# analog_part.net
KiCad netlist of a schematic drawn in Altium Designer
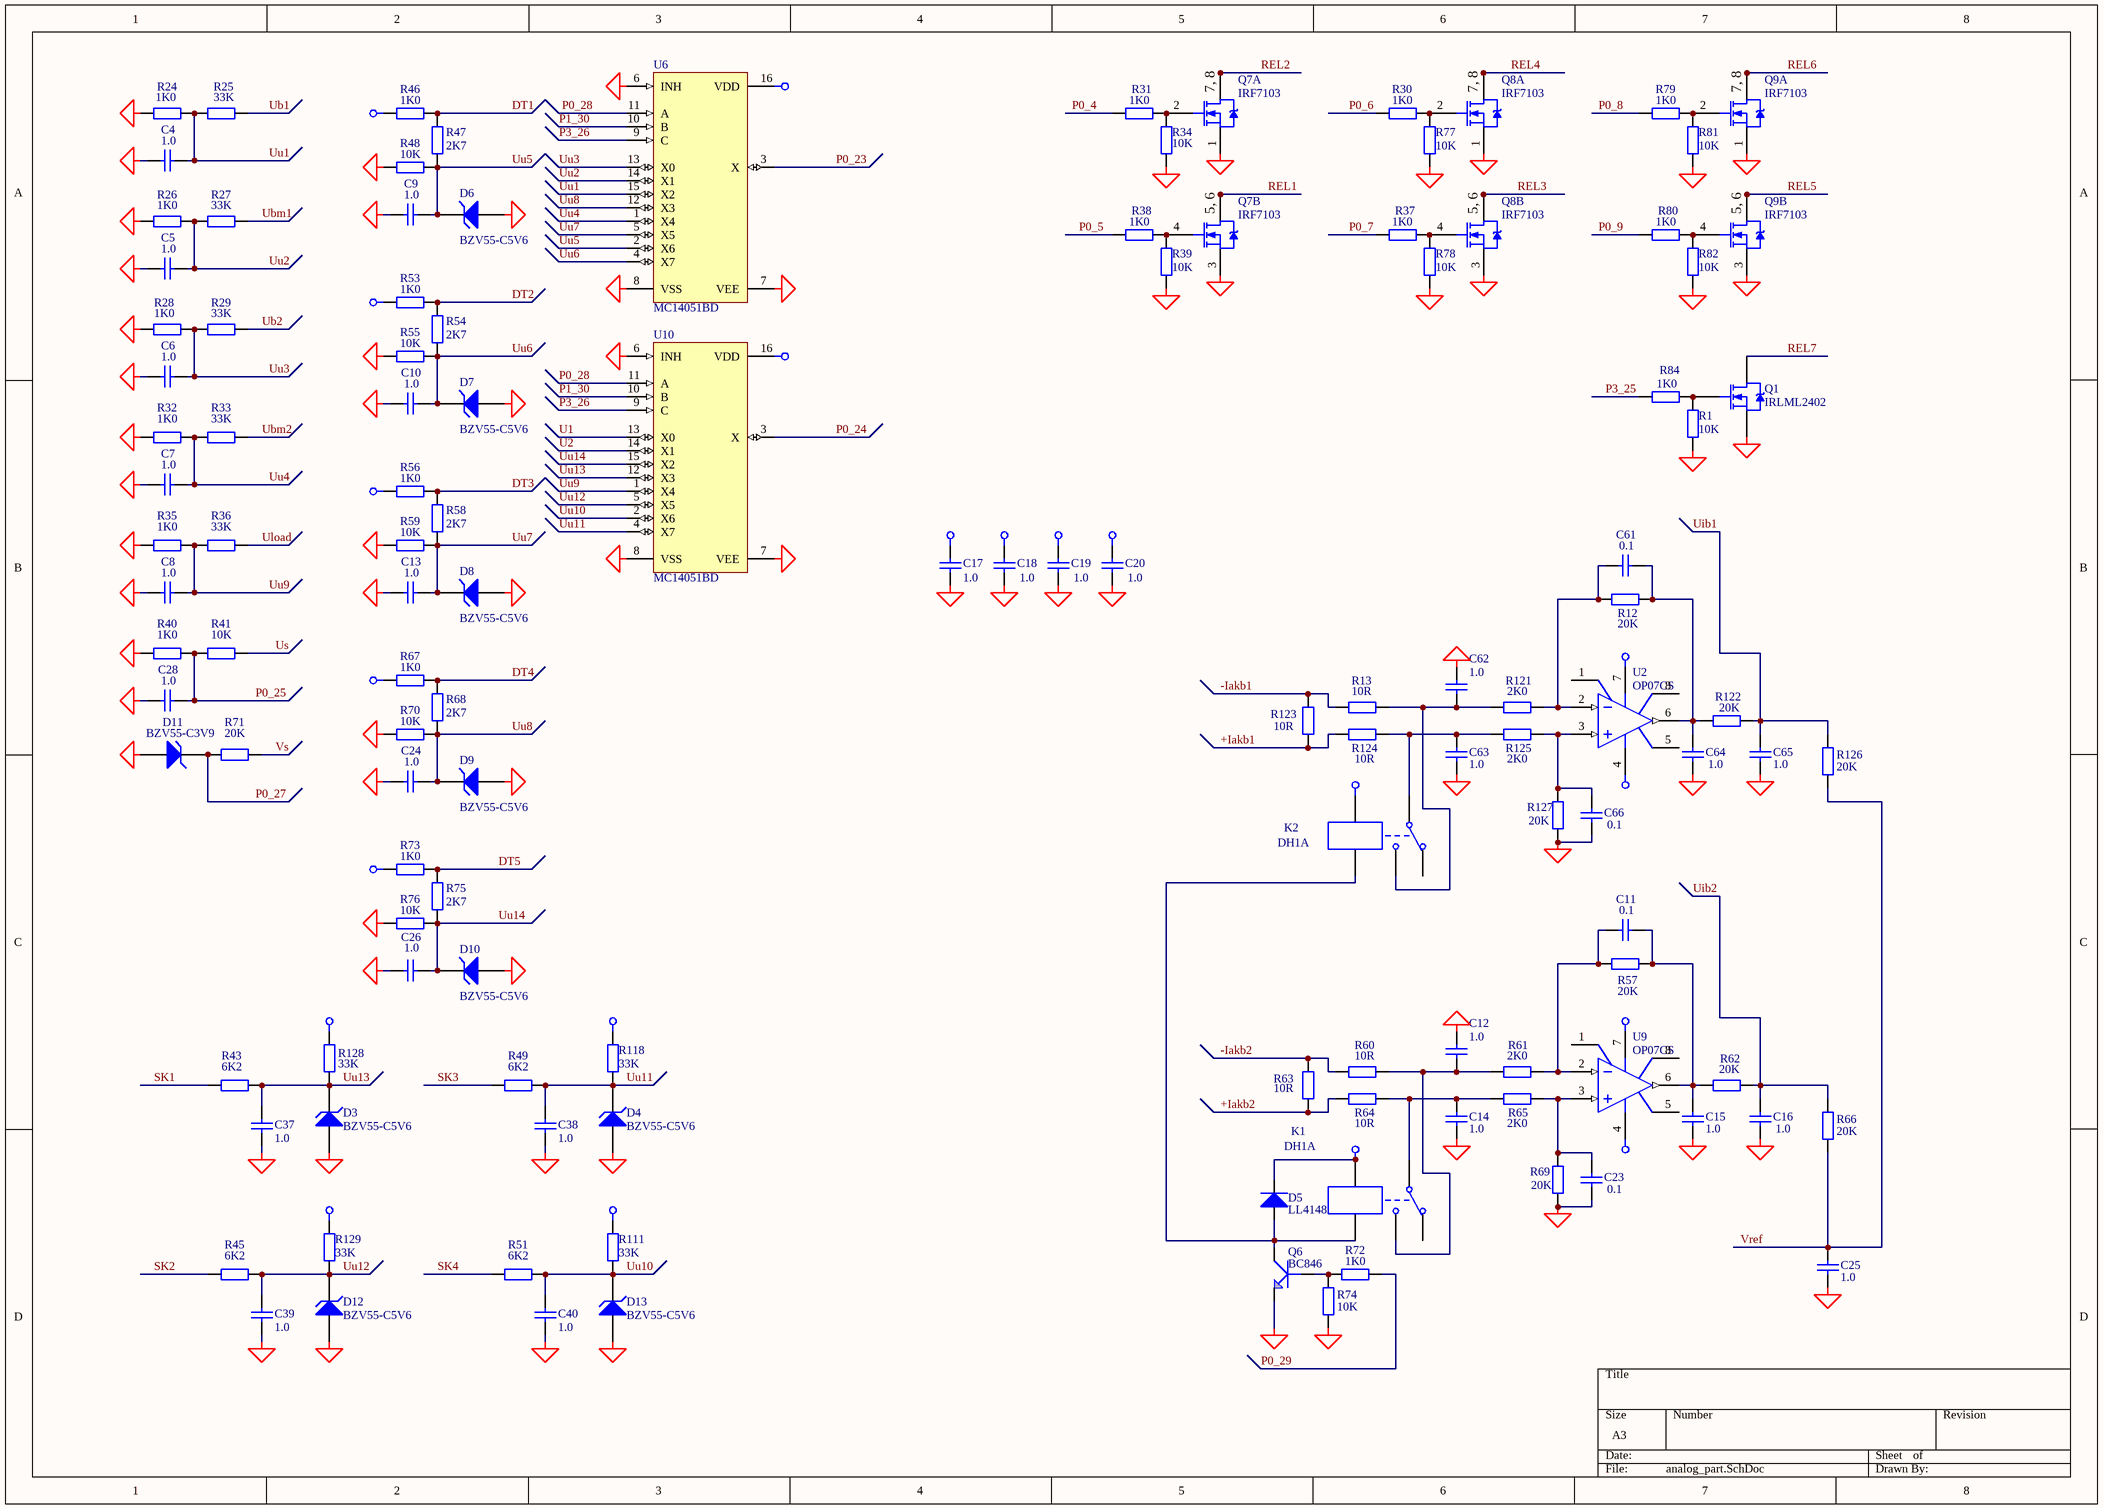
[diagram p0: analog_part.SchDoc]

(export (version "E")
  (design (tool "Eeschema 10.0.6"))
  (components
    (comp (ref "C4")
      (value "1.0")
      (footprint "_1206")
      (description "Capacitor")
      (fields (field (name "MANUFACTURER") "Generic Components"))
      (libsource (lib "Miscellaneous Devices") (part "Cap Semi"))
    )
    (comp (ref "C5")
      (value "1.0")
      (footprint "_1206")
      (description "Capacitor")
      (fields (field (name "MANUFACTURER") "Generic Components"))
      (libsource (lib "Miscellaneous Devices") (part "Cap Semi"))
    )
    (comp (ref "C6")
      (value "1.0")
      (footprint "_1206")
      (description "Capacitor")
      (fields (field (name "MANUFACTURER") "Generic Components"))
      (libsource (lib "Miscellaneous Devices") (part "Cap Semi"))
    )
    (comp (ref "C7")
      (value "1.0")
      (footprint "_1206")
      (description "Capacitor")
      (fields (field (name "MANUFACTURER") "Generic Components"))
      (libsource (lib "Miscellaneous Devices") (part "Cap Semi"))
    )
    (comp (ref "C8")
      (value "1.0")
      (footprint "_1206")
      (description "Capacitor")
      (fields (field (name "MANUFACTURER") "Generic Components"))
      (libsource (lib "Miscellaneous Devices") (part "Cap Semi"))
    )
    (comp (ref "C9")
      (value "1.0")
      (footprint "_1206")
      (description "Capacitor")
      (fields (field (name "MANUFACTURER") "Generic Components"))
      (libsource (lib "Miscellaneous Devices") (part "Cap Semi"))
    )
    (comp (ref "C10")
      (value "1.0")
      (footprint "_1206")
      (description "Capacitor")
      (fields (field (name "MANUFACTURER") "Generic Components"))
      (libsource (lib "Miscellaneous Devices") (part "Cap Semi"))
    )
    (comp (ref "C11")
      (value "0.1")
      (footprint "_1206")
      (description "Capacitor")
      (fields (field (name "MANUFACTURER") "Generic Components"))
      (libsource (lib "Miscellaneous Devices") (part "Cap Semi"))
    )
    (comp (ref "C12")
      (value "1.0")
      (footprint "_1206")
      (description "Capacitor")
      (fields (field (name "MANUFACTURER") "Generic Components"))
      (libsource (lib "Miscellaneous Devices") (part "Cap Semi"))
    )
    (comp (ref "C13")
      (value "1.0")
      (footprint "_1206")
      (description "Capacitor")
      (fields (field (name "MANUFACTURER") "Generic Components"))
      (libsource (lib "Miscellaneous Devices") (part "Cap Semi"))
    )
    (comp (ref "C14")
      (value "1.0")
      (footprint "_1206")
      (description "Capacitor")
      (fields (field (name "MANUFACTURER") "Generic Components"))
      (libsource (lib "Miscellaneous Devices") (part "Cap Semi"))
    )
    (comp (ref "C15")
      (value "1.0")
      (footprint "_1206")
      (description "Capacitor")
      (fields (field (name "MANUFACTURER") "Generic Components"))
      (libsource (lib "Miscellaneous Devices") (part "Cap Semi"))
    )
    (comp (ref "C16")
      (value "1.0")
      (footprint "_1206")
      (description "Capacitor")
      (fields (field (name "MANUFACTURER") "Generic Components"))
      (libsource (lib "Miscellaneous Devices") (part "Cap Semi"))
    )
    (comp (ref "C17")
      (value "1.0")
      (footprint "_1206")
      (description "Capacitor")
      (fields (field (name "MANUFACTURER") "Generic Components"))
      (libsource (lib "Miscellaneous Devices") (part "Cap Semi"))
    )
    (comp (ref "C18")
      (value "1.0")
      (footprint "_1206")
      (description "Capacitor")
      (fields (field (name "MANUFACTURER") "Generic Components"))
      (libsource (lib "Miscellaneous Devices") (part "Cap Semi"))
    )
    (comp (ref "C19")
      (value "1.0")
      (footprint "_1206")
      (description "Capacitor")
      (fields (field (name "MANUFACTURER") "Generic Components"))
      (libsource (lib "Miscellaneous Devices") (part "Cap Semi"))
    )
    (comp (ref "C20")
      (value "1.0")
      (footprint "_1206")
      (description "Capacitor")
      (fields (field (name "MANUFACTURER") "Generic Components"))
      (libsource (lib "Miscellaneous Devices") (part "Cap Semi"))
    )
    (comp (ref "C23")
      (value "0.1")
      (footprint "_1206")
      (description "Capacitor")
      (fields (field (name "MANUFACTURER") "Generic Components"))
      (libsource (lib "Miscellaneous Devices") (part "Cap Semi"))
    )
    (comp (ref "C24")
      (value "1.0")
      (footprint "_1206")
      (description "Capacitor")
      (fields (field (name "MANUFACTURER") "Generic Components"))
      (libsource (lib "Miscellaneous Devices") (part "Cap Semi"))
    )
    (comp (ref "C25")
      (value "1.0")
      (footprint "_1206")
      (description "Capacitor")
      (fields (field (name "MANUFACTURER") "Generic Components"))
      (libsource (lib "Miscellaneous Devices") (part "Cap Semi"))
    )
    (comp (ref "C26")
      (value "1.0")
      (footprint "_1206")
      (description "Capacitor")
      (fields (field (name "MANUFACTURER") "Generic Components"))
      (libsource (lib "Miscellaneous Devices") (part "Cap Semi"))
    )
    (comp (ref "C28")
      (value "1.0")
      (footprint "_1206")
      (description "Capacitor")
      (fields (field (name "MANUFACTURER") "Generic Components"))
      (libsource (lib "Miscellaneous Devices") (part "Cap Semi"))
    )
    (comp (ref "C37")
      (value "1.0")
      (footprint "_1206")
      (description "Capacitor")
      (fields (field (name "MANUFACTURER") "Generic Components"))
      (libsource (lib "Miscellaneous Devices") (part "Cap Semi"))
    )
    (comp (ref "C38")
      (value "1.0")
      (footprint "_1206")
      (description "Capacitor")
      (fields (field (name "MANUFACTURER") "Generic Components"))
      (libsource (lib "Miscellaneous Devices") (part "Cap Semi"))
    )
    (comp (ref "C39")
      (value "1.0")
      (footprint "_1206")
      (description "Capacitor")
      (fields (field (name "MANUFACTURER") "Generic Components"))
      (libsource (lib "Miscellaneous Devices") (part "Cap Semi"))
    )
    (comp (ref "C40")
      (value "1.0")
      (footprint "_1206")
      (description "Capacitor")
      (fields (field (name "MANUFACTURER") "Generic Components"))
      (libsource (lib "Miscellaneous Devices") (part "Cap Semi"))
    )
    (comp (ref "C61")
      (value "0.1")
      (footprint "_1206")
      (description "Capacitor")
      (fields (field (name "MANUFACTURER") "Generic Components"))
      (libsource (lib "Miscellaneous Devices") (part "Cap Semi"))
    )
    (comp (ref "C62")
      (value "1.0")
      (footprint "_1206")
      (description "Capacitor")
      (fields (field (name "MANUFACTURER") "Generic Components"))
      (libsource (lib "Miscellaneous Devices") (part "Cap Semi"))
    )
    (comp (ref "C63")
      (value "1.0")
      (footprint "_1206")
      (description "Capacitor")
      (fields (field (name "MANUFACTURER") "Generic Components"))
      (libsource (lib "Miscellaneous Devices") (part "Cap Semi"))
    )
    (comp (ref "C64")
      (value "1.0")
      (footprint "_1206")
      (description "Capacitor")
      (fields (field (name "MANUFACTURER") "Generic Components"))
      (libsource (lib "Miscellaneous Devices") (part "Cap Semi"))
    )
    (comp (ref "C65")
      (value "1.0")
      (footprint "_1206")
      (description "Capacitor")
      (fields (field (name "MANUFACTURER") "Generic Components"))
      (libsource (lib "Miscellaneous Devices") (part "Cap Semi"))
    )
    (comp (ref "C66")
      (value "0.1")
      (footprint "_1206")
      (description "Capacitor")
      (fields (field (name "MANUFACTURER") "Generic Components"))
      (libsource (lib "Miscellaneous Devices") (part "Cap Semi"))
    )
    (comp (ref "D3")
      (value "BZV55-C5V6")
      (footprint "_1206d")
      (description "Zener Diode")
      (fields (field (name "MANUFACTURER") "Generic Components"))
      (libsource (lib "Miscellaneous Devices") (part "D Zener"))
    )
    (comp (ref "D4")
      (value "BZV55-C5V6")
      (footprint "_1206d")
      (description "Zener Diode")
      (fields (field (name "MANUFACTURER") "Generic Components"))
      (libsource (lib "Miscellaneous Devices") (part "D Zener"))
    )
    (comp (ref "D5")
      (value "LL4148")
      (footprint "_1206d")
      (description "Diode")
      (fields (field (name "MANUFACTURER") "Generic Components"))
      (libsource (lib "Pal") (part "Diode"))
    )
    (comp (ref "D6")
      (value "BZV55-C5V6")
      (footprint "_1206d")
      (description "Zener Diode")
      (fields (field (name "MANUFACTURER") "Generic Components"))
      (libsource (lib "Miscellaneous Devices") (part "D Zener"))
    )
    (comp (ref "D7")
      (value "BZV55-C5V6")
      (footprint "_1206d")
      (description "Zener Diode")
      (fields (field (name "MANUFACTURER") "Generic Components"))
      (libsource (lib "Miscellaneous Devices") (part "D Zener"))
    )
    (comp (ref "D8")
      (value "BZV55-C5V6")
      (footprint "_1206d")
      (description "Zener Diode")
      (fields (field (name "MANUFACTURER") "Generic Components"))
      (libsource (lib "Miscellaneous Devices") (part "D Zener"))
    )
    (comp (ref "D9")
      (value "BZV55-C5V6")
      (footprint "_1206d")
      (description "Zener Diode")
      (fields (field (name "MANUFACTURER") "Generic Components"))
      (libsource (lib "Miscellaneous Devices") (part "D Zener"))
    )
    (comp (ref "D10")
      (value "BZV55-C5V6")
      (footprint "_1206d")
      (description "Zener Diode")
      (fields (field (name "MANUFACTURER") "Generic Components"))
      (libsource (lib "Miscellaneous Devices") (part "D Zener"))
    )
    (comp (ref "D11")
      (value "BZV55-C3V9")
      (footprint "_1206d")
      (description "Zener Diode")
      (fields (field (name "MANUFACTURER") "Generic Components"))
      (libsource (lib "Miscellaneous Devices") (part "D Zener"))
    )
    (comp (ref "D12")
      (value "BZV55-C5V6")
      (footprint "_1206d")
      (description "Zener Diode")
      (fields (field (name "MANUFACTURER") "Generic Components"))
      (libsource (lib "Miscellaneous Devices") (part "D Zener"))
    )
    (comp (ref "D13")
      (value "BZV55-C5V6")
      (footprint "_1206d")
      (description "Zener Diode")
      (fields (field (name "MANUFACTURER") "Generic Components"))
      (libsource (lib "Miscellaneous Devices") (part "D Zener"))
    )
    (comp (ref "K1")
      (value "DH1A")
      (footprint "kuan")
      (description "Relay")
      (fields (field (name "MANUFACTURER") "Generic Components"))
      (libsource (lib "PAL") (part "BS115"))
    )
    (comp (ref "K2")
      (value "DH1A")
      (footprint "kuan")
      (description "Relay")
      (fields (field (name "MANUFACTURER") "Generic Components"))
      (libsource (lib "PAL") (part "BS115"))
    )
    (comp (ref "Q1")
      (value "IRLML2402")
      (footprint "SO-G3/Z3.3")
      (description "HEXFET Power MOSFET")
      (fields (field (name "MANUFACTURER") "International Rectifier"))
      (libsource (lib "IR Discrete MOSFET") (part "IRLML2402"))
    )
    (comp (ref "Q6")
      (value "BC846")
      (footprint "SO-G3")
      (description "Bipolar transistor")
      (libsource (lib "MAIN") (part "GT122"))
    )
    (comp (ref "Q7")
      (value "IRF7103")
      (footprint "SO-G8/Y2.2")
      (description "FET")
      (fields (field (name "MANUFACTURER") "International Rectifier"))
      (libsource (lib "IR Discrete MOSFET") (part "IRF7301"))
    )
    (comp (ref "Q8")
      (value "IRF7103")
      (footprint "SO-G8/Y2.2")
      (description "FET")
      (fields (field (name "MANUFACTURER") "International Rectifier"))
      (libsource (lib "IR Discrete MOSFET") (part "IRF7301"))
    )
    (comp (ref "Q9")
      (value "IRF7103")
      (footprint "SO-G8/Y2.2")
      (description "FET")
      (fields (field (name "MANUFACTURER") "International Rectifier"))
      (libsource (lib "IR Discrete MOSFET") (part "IRF7301"))
    )
    (comp (ref "R1")
      (value "10K")
      (footprint "_1206")
      (description "Resistor")
      (fields (field (name "MANUFACTURER") "Generic Components"))
      (libsource (lib "") (part "Res2_3"))
    )
    (comp (ref "R12")
      (value "20K")
      (footprint "_1206")
      (description "Resistor")
      (fields (field (name "MANUFACTURER") "Generic Components"))
      (libsource (lib "") (part "Res2_2"))
    )
    (comp (ref "R13")
      (value "10R")
      (footprint "_1206")
      (description "Resistor")
      (fields (field (name "MANUFACTURER") "Generic Components"))
      (libsource (lib "") (part "Res2_1"))
    )
    (comp (ref "R24")
      (value "1K0")
      (footprint "_1206")
      (description "Resistor")
      (fields (field (name "MANUFACTURER") "Generic Components"))
      (libsource (lib "") (part "Res2_1"))
    )
    (comp (ref "R25")
      (value "33K")
      (footprint "_1206")
      (description "Resistor")
      (fields (field (name "MANUFACTURER") "Generic Components"))
      (libsource (lib "") (part "Res2_2"))
    )
    (comp (ref "R26")
      (value "1K0")
      (footprint "_1206")
      (description "Resistor")
      (fields (field (name "MANUFACTURER") "Generic Components"))
      (libsource (lib "") (part "Res2_1"))
    )
    (comp (ref "R27")
      (value "33K")
      (footprint "_1206")
      (description "Resistor")
      (fields (field (name "MANUFACTURER") "Generic Components"))
      (libsource (lib "") (part "Res2_2"))
    )
    (comp (ref "R28")
      (value "1K0")
      (footprint "_1206")
      (description "Resistor")
      (fields (field (name "MANUFACTURER") "Generic Components"))
      (libsource (lib "") (part "Res2_1"))
    )
    (comp (ref "R29")
      (value "33K")
      (footprint "_1206")
      (description "Resistor")
      (fields (field (name "MANUFACTURER") "Generic Components"))
      (libsource (lib "") (part "Res2_2"))
    )
    (comp (ref "R30")
      (value "1K0")
      (footprint "_1206")
      (description "Resistor")
      (fields (field (name "MANUFACTURER") "Generic Components"))
      (libsource (lib "") (part "Res2_2"))
    )
    (comp (ref "R31")
      (value "1K0")
      (footprint "_1206")
      (description "Resistor")
      (fields (field (name "MANUFACTURER") "Generic Components"))
      (libsource (lib "") (part "Res2_2"))
    )
    (comp (ref "R32")
      (value "1K0")
      (footprint "_1206")
      (description "Resistor")
      (fields (field (name "MANUFACTURER") "Generic Components"))
      (libsource (lib "") (part "Res2_1"))
    )
    (comp (ref "R33")
      (value "33K")
      (footprint "_1206")
      (description "Resistor")
      (fields (field (name "MANUFACTURER") "Generic Components"))
      (libsource (lib "") (part "Res2_2"))
    )
    (comp (ref "R34")
      (value "10K")
      (footprint "_1206")
      (description "Resistor")
      (fields (field (name "MANUFACTURER") "Generic Components"))
      (libsource (lib "") (part "Res2_3"))
    )
    (comp (ref "R35")
      (value "1K0")
      (footprint "_1206")
      (description "Resistor")
      (fields (field (name "MANUFACTURER") "Generic Components"))
      (libsource (lib "") (part "Res2_1"))
    )
    (comp (ref "R36")
      (value "33K")
      (footprint "_1206")
      (description "Resistor")
      (fields (field (name "MANUFACTURER") "Generic Components"))
      (libsource (lib "") (part "Res2_2"))
    )
    (comp (ref "R37")
      (value "1K0")
      (footprint "_1206")
      (description "Resistor")
      (fields (field (name "MANUFACTURER") "Generic Components") (field (name "ALTIUM_VALUE") "1K0"))
      (libsource (lib "") (part "Res2_2"))
    )
    (comp (ref "R38")
      (value "1K0")
      (footprint "_1206")
      (description "Resistor")
      (fields (field (name "MANUFACTURER") "Generic Components"))
      (libsource (lib "") (part "Res2_2"))
    )
    (comp (ref "R39")
      (value "10K")
      (footprint "_1206")
      (description "Resistor")
      (fields (field (name "MANUFACTURER") "Generic Components"))
      (libsource (lib "") (part "Res2_3"))
    )
    (comp (ref "R40")
      (value "1K0")
      (footprint "_1206")
      (description "Resistor")
      (fields (field (name "MANUFACTURER") "Generic Components"))
      (libsource (lib "") (part "Res2_1"))
    )
    (comp (ref "R41")
      (value "10K")
      (footprint "_1206")
      (description "Resistor")
      (fields (field (name "MANUFACTURER") "Generic Components"))
      (libsource (lib "") (part "Res2_2"))
    )
    (comp (ref "R43")
      (value "6K2")
      (footprint "_1206")
      (description "Resistor")
      (fields (field (name "MANUFACTURER") "Generic Components"))
      (libsource (lib "") (part "Res2_2"))
    )
    (comp (ref "R45")
      (value "6K2")
      (footprint "_1206")
      (description "Resistor")
      (fields (field (name "MANUFACTURER") "Generic Components"))
      (libsource (lib "") (part "Res2_2"))
    )
    (comp (ref "R46")
      (value "1K0")
      (footprint "_0805")
      (description "Resistor")
      (fields (field (name "MANUFACTURER") "Generic Components"))
      (libsource (lib "") (part "Res2_1"))
    )
    (comp (ref "R47")
      (value "2K7")
      (footprint "_1206")
      (description "Resistor")
      (fields (field (name "MANUFACTURER") "Generic Components"))
      (libsource (lib "Miscellaneous Devices") (part "Res2"))
    )
    (comp (ref "R48")
      (value "10K")
      (footprint "_1206")
      (description "Resistor")
      (fields (field (name "MANUFACTURER") "Generic Components"))
      (libsource (lib "") (part "Res2_2"))
    )
    (comp (ref "R49")
      (value "6K2")
      (footprint "_1206")
      (description "Resistor")
      (fields (field (name "MANUFACTURER") "Generic Components"))
      (libsource (lib "") (part "Res2_2"))
    )
    (comp (ref "R51")
      (value "6K2")
      (footprint "_1206")
      (description "Resistor")
      (fields (field (name "MANUFACTURER") "Generic Components"))
      (libsource (lib "") (part "Res2_2"))
    )
    (comp (ref "R53")
      (value "1K0")
      (footprint "_0805")
      (description "Resistor")
      (fields (field (name "MANUFACTURER") "Generic Components") (field (name "ALTIUM_VALUE") "1K0"))
      (libsource (lib "") (part "Res2_1"))
    )
    (comp (ref "R54")
      (value "2K7")
      (footprint "_1206")
      (description "Resistor")
      (fields (field (name "MANUFACTURER") "Generic Components"))
      (libsource (lib "Miscellaneous Devices") (part "Res2"))
    )
    (comp (ref "R55")
      (value "10K")
      (footprint "_1206")
      (description "Resistor")
      (fields (field (name "MANUFACTURER") "Generic Components"))
      (libsource (lib "") (part "Res2_2"))
    )
    (comp (ref "R56")
      (value "1K0")
      (footprint "_0805")
      (description "Resistor")
      (fields (field (name "MANUFACTURER") "Generic Components") (field (name "ALTIUM_VALUE") "1K0"))
      (libsource (lib "") (part "Res2_1"))
    )
    (comp (ref "R57")
      (value "20K")
      (footprint "_1206")
      (description "Resistor")
      (fields (field (name "MANUFACTURER") "Generic Components"))
      (libsource (lib "") (part "Res2_2"))
    )
    (comp (ref "R58")
      (value "2K7")
      (footprint "_1206")
      (description "Resistor")
      (fields (field (name "MANUFACTURER") "Generic Components"))
      (libsource (lib "Miscellaneous Devices") (part "Res2"))
    )
    (comp (ref "R59")
      (value "10K")
      (footprint "_1206")
      (description "Resistor")
      (fields (field (name "MANUFACTURER") "Generic Components"))
      (libsource (lib "") (part "Res2_2"))
    )
    (comp (ref "R60")
      (value "10R")
      (footprint "_1206")
      (description "Resistor")
      (fields (field (name "MANUFACTURER") "Generic Components"))
      (libsource (lib "") (part "Res2_1"))
    )
    (comp (ref "R61")
      (value "2K0")
      (footprint "_1206")
      (description "Resistor")
      (fields (field (name "MANUFACTURER") "Generic Components"))
      (libsource (lib "") (part "Res2_2"))
    )
    (comp (ref "R62")
      (value "20K")
      (footprint "_1206")
      (description "Resistor")
      (fields (field (name "MANUFACTURER") "Generic Components"))
      (libsource (lib "") (part "Res2_2"))
    )
    (comp (ref "R63")
      (value "10R")
      (footprint "_1206")
      (description "Resistor")
      (fields (field (name "MANUFACTURER") "Generic Components"))
      (libsource (lib "") (part "Res2_3"))
    )
    (comp (ref "R64")
      (value "10R")
      (footprint "_1206")
      (description "Resistor")
      (fields (field (name "MANUFACTURER") "Generic Components"))
      (libsource (lib "") (part "Res2_1"))
    )
    (comp (ref "R65")
      (value "2K0")
      (footprint "_1206")
      (description "Resistor")
      (fields (field (name "MANUFACTURER") "Generic Components"))
      (libsource (lib "") (part "Res2_2"))
    )
    (comp (ref "R66")
      (value "20K")
      (footprint "_1206")
      (description "Resistor")
      (fields (field (name "MANUFACTURER") "Generic Components"))
      (libsource (lib "") (part "Res2_1"))
    )
    (comp (ref "R67")
      (value "1K0")
      (footprint "_0805")
      (description "Resistor")
      (fields (field (name "MANUFACTURER") "Generic Components") (field (name "ALTIUM_VALUE") "1K0"))
      (libsource (lib "") (part "Res2_1"))
    )
    (comp (ref "R68")
      (value "2K7")
      (footprint "_1206")
      (description "Resistor")
      (fields (field (name "MANUFACTURER") "Generic Components"))
      (libsource (lib "Miscellaneous Devices") (part "Res2"))
    )
    (comp (ref "R69")
      (value "20K")
      (footprint "_1206")
      (description "Resistor")
      (fields (field (name "MANUFACTURER") "Generic Components"))
      (libsource (lib "") (part "Res2_3"))
    )
    (comp (ref "R70")
      (value "10K")
      (footprint "_1206")
      (description "Resistor")
      (fields (field (name "MANUFACTURER") "Generic Components"))
      (libsource (lib "") (part "Res2_2"))
    )
    (comp (ref "R71")
      (value "20K")
      (footprint "_1206")
      (description "Resistor")
      (fields (field (name "MANUFACTURER") "Generic Components"))
      (libsource (lib "") (part "Res2_2"))
    )
    (comp (ref "R72")
      (value "1K0")
      (footprint "_1206")
      (description "Resistor")
      (fields (field (name "MANUFACTURER") "Generic Components"))
      (libsource (lib "Miscellaneous Devices") (part "Res2"))
    )
    (comp (ref "R73")
      (value "1K0")
      (footprint "_0805")
      (description "Resistor")
      (fields (field (name "MANUFACTURER") "Generic Components") (field (name "ALTIUM_VALUE") "1K0"))
      (libsource (lib "") (part "Res2_1"))
    )
    (comp (ref "R74")
      (value "10K")
      (footprint "_1206")
      (description "Resistor")
      (fields (field (name "MANUFACTURER") "Generic Components"))
      (libsource (lib "") (part "Res2_2"))
    )
    (comp (ref "R75")
      (value "2K7")
      (footprint "_1206")
      (description "Resistor")
      (fields (field (name "MANUFACTURER") "Generic Components"))
      (libsource (lib "Miscellaneous Devices") (part "Res2"))
    )
    (comp (ref "R76")
      (value "10K")
      (footprint "_1206")
      (description "Resistor")
      (fields (field (name "MANUFACTURER") "Generic Components"))
      (libsource (lib "") (part "Res2_2"))
    )
    (comp (ref "R77")
      (value "10K")
      (footprint "_1206")
      (description "Resistor")
      (fields (field (name "MANUFACTURER") "Generic Components"))
      (libsource (lib "") (part "Res2_3"))
    )
    (comp (ref "R78")
      (value "10K")
      (footprint "_1206")
      (description "Resistor")
      (fields (field (name "MANUFACTURER") "Generic Components"))
      (libsource (lib "") (part "Res2_3"))
    )
    (comp (ref "R79")
      (value "1K0")
      (footprint "_1206")
      (description "Resistor")
      (fields (field (name "MANUFACTURER") "Generic Components"))
      (libsource (lib "") (part "Res2_2"))
    )
    (comp (ref "R80")
      (value "1K0")
      (footprint "_1206")
      (description "Resistor")
      (fields (field (name "MANUFACTURER") "Generic Components") (field (name "ALTIUM_VALUE") "1K0"))
      (libsource (lib "") (part "Res2_2"))
    )
    (comp (ref "R81")
      (value "10K")
      (footprint "_1206")
      (description "Resistor")
      (fields (field (name "MANUFACTURER") "Generic Components"))
      (libsource (lib "") (part "Res2_3"))
    )
    (comp (ref "R82")
      (value "10K")
      (footprint "_1206")
      (description "Resistor")
      (fields (field (name "MANUFACTURER") "Generic Components"))
      (libsource (lib "") (part "Res2_3"))
    )
    (comp (ref "R84")
      (value "1K0")
      (footprint "_1206")
      (description "Resistor")
      (fields (field (name "MANUFACTURER") "Generic Components"))
      (libsource (lib "") (part "Res2_2"))
    )
    (comp (ref "R111")
      (value "33K")
      (footprint "_1206")
      (description "Resistor")
      (fields (field (name "MANUFACTURER") "Generic Components"))
      (libsource (lib "") (part "Res2_1"))
    )
    (comp (ref "R118")
      (value "33K")
      (footprint "_1206")
      (description "Resistor")
      (fields (field (name "MANUFACTURER") "Generic Components"))
      (libsource (lib "") (part "Res2_1"))
    )
    (comp (ref "R121")
      (value "2K0")
      (footprint "_1206")
      (description "Resistor")
      (fields (field (name "MANUFACTURER") "Generic Components"))
      (libsource (lib "") (part "Res2_2"))
    )
    (comp (ref "R122")
      (value "20K")
      (footprint "_1206")
      (description "Resistor")
      (fields (field (name "MANUFACTURER") "Generic Components"))
      (libsource (lib "") (part "Res2_2"))
    )
    (comp (ref "R123")
      (value "10R")
      (footprint "_1206")
      (description "Resistor")
      (fields (field (name "MANUFACTURER") "Generic Components"))
      (libsource (lib "") (part "Res2_3"))
    )
    (comp (ref "R124")
      (value "10R")
      (footprint "_1206")
      (description "Resistor")
      (fields (field (name "MANUFACTURER") "Generic Components"))
      (libsource (lib "") (part "Res2_1"))
    )
    (comp (ref "R125")
      (value "2K0")
      (footprint "_1206")
      (description "Resistor")
      (fields (field (name "MANUFACTURER") "Generic Components"))
      (libsource (lib "") (part "Res2_2"))
    )
    (comp (ref "R126")
      (value "20K")
      (footprint "_1206")
      (description "Resistor")
      (fields (field (name "MANUFACTURER") "Generic Components"))
      (libsource (lib "") (part "Res2_1"))
    )
    (comp (ref "R127")
      (value "20K")
      (footprint "_1206")
      (description "Resistor")
      (fields (field (name "MANUFACTURER") "Generic Components"))
      (libsource (lib "") (part "Res2_3"))
    )
    (comp (ref "R128")
      (value "33K")
      (footprint "_1206")
      (description "Resistor")
      (fields (field (name "MANUFACTURER") "Generic Components"))
      (libsource (lib "Miscellaneous Devices") (part "Res2"))
    )
    (comp (ref "R129")
      (value "33K")
      (footprint "_1206")
      (description "Resistor")
      (fields (field (name "MANUFACTURER") "Generic Components"))
      (libsource (lib "") (part "Res2_1"))
    )
    (comp (ref "U2")
      (value "OP07CS")
      (footprint "SO-G8")
      (description "Operational Amplifier")
      (fields (field (name "MANUFACTURER") "Analog Devices"))
      (libsource (lib "AD Operational Amplifier") (part "OP07CS"))
    )
    (comp (ref "U6")
      (value "MC14051BD")
      (footprint "SO-G16/C5.85")
      (description "Multiplexer")
      (fields (field (name "MANUFACTURER") "ON Semiconductor"))
      (libsource (lib "ON Semi Logic Multiplexer") (part "MC14051BD"))
    )
    (comp (ref "U9")
      (value "OP07CS")
      (footprint "SO-G8")
      (description "Operational Amplifier")
      (fields (field (name "MANUFACTURER") "Analog Devices"))
      (libsource (lib "AD Operational Amplifier") (part "OP07CS"))
    )
    (comp (ref "U10")
      (value "MC14051BD")
      (footprint "SO-G16/C5.85")
      (description "Multiplexer")
      (fields (field (name "MANUFACTURER") "ON Semiconductor"))
      (libsource (lib "ON Semi Logic Multiplexer") (part "MC14051BD"))
    )
  )
  (nets
    (net (code "1") (name "+3v3") (class "Default")
      (node (ref "R111") (pin "1") (pinfunction "1_1") (pintype "passive"))
      (node (ref "R118") (pin "1") (pinfunction "1_1") (pintype "passive"))
      (node (ref "R128") (pin "1") (pinfunction "1_1") (pintype "passive"))
      (node (ref "R129") (pin "1") (pinfunction "1_1") (pintype "passive"))
    )
    (net (code "2") (name "+5v") (class "Default")
      (node (ref "C17") (pin "2") (pinfunction "2_2") (pintype "passive"))
      (node (ref "C19") (pin "2") (pinfunction "2_2") (pintype "passive"))
      (node (ref "D5") (pin "2") (pinfunction "K_2") (pintype "passive"))
      (node (ref "K1") (pin "4") (pinfunction "4_4") (pintype "passive"))
      (node (ref "K2") (pin "4") (pinfunction "4_4") (pintype "passive"))
      (node (ref "R46") (pin "2") (pinfunction "2_2") (pintype "passive"))
      (node (ref "R53") (pin "2") (pinfunction "2_2") (pintype "passive"))
      (node (ref "R56") (pin "2") (pinfunction "2_2") (pintype "passive"))
      (node (ref "R67") (pin "2") (pinfunction "2_2") (pintype "passive"))
      (node (ref "R73") (pin "2") (pinfunction "2_2") (pintype "passive"))
      (node (ref "U10") (pin "16") (pinfunction "VDD_16") (pintype "power_in"))
      (node (ref "U2") (pin "7") (pinfunction "V+_7") (pintype "power_in"))
      (node (ref "U6") (pin "16") (pinfunction "VDD_16") (pintype "power_in"))
      (node (ref "U9") (pin "7") (pinfunction "V+_7") (pintype "power_in"))
    )
    (net (code "3") (name "-5v") (class "Default")
      (node (ref "C18") (pin "2") (pinfunction "2_2") (pintype "passive"))
      (node (ref "U2") (pin "4") (pinfunction "V-_4") (pintype "power_in"))
      (node (ref "U9") (pin "4") (pinfunction "V-_4") (pintype "power_in"))
    )
    (net (code "4") (name "/+Iakb1") (class "Default")
      (node (ref "R123") (pin "1") (pinfunction "1_1") (pintype "passive"))
      (node (ref "R124") (pin "2") (pinfunction "2_2") (pintype "passive"))
    )
    (net (code "5") (name "/+Iakb2") (class "Default")
      (node (ref "R63") (pin "1") (pinfunction "1_1") (pintype "passive"))
      (node (ref "R64") (pin "2") (pinfunction "2_2") (pintype "passive"))
    )
    (net (code "6") (name "/-Iakb1") (class "Default")
      (node (ref "R123") (pin "2") (pinfunction "2_2") (pintype "passive"))
      (node (ref "R13") (pin "2") (pinfunction "2_2") (pintype "passive"))
    )
    (net (code "7") (name "/-Iakb2") (class "Default")
      (node (ref "R60") (pin "2") (pinfunction "2_2") (pintype "passive"))
      (node (ref "R63") (pin "2") (pinfunction "2_2") (pintype "passive"))
    )
    (net (code "8") (name "/DT1") (class "Default")
      (node (ref "R46") (pin "1") (pinfunction "1_1") (pintype "passive"))
      (node (ref "R47") (pin "1") (pinfunction "1_1") (pintype "passive"))
    )
    (net (code "9") (name "/DT2") (class "Default")
      (node (ref "R53") (pin "1") (pinfunction "1_1") (pintype "passive"))
      (node (ref "R54") (pin "1") (pinfunction "1_1") (pintype "passive"))
    )
    (net (code "10") (name "/DT3") (class "Default")
      (node (ref "R56") (pin "1") (pinfunction "1_1") (pintype "passive"))
      (node (ref "R58") (pin "1") (pinfunction "1_1") (pintype "passive"))
    )
    (net (code "11") (name "/DT4") (class "Default")
      (node (ref "R67") (pin "1") (pinfunction "1_1") (pintype "passive"))
      (node (ref "R68") (pin "1") (pinfunction "1_1") (pintype "passive"))
    )
    (net (code "12") (name "/DT5") (class "Default")
      (node (ref "R73") (pin "1") (pinfunction "1_1") (pintype "passive"))
      (node (ref "R75") (pin "1") (pinfunction "1_1") (pintype "passive"))
    )
    (net (code "13") (name "/P0_4") (class "Default")
      (node (ref "R31") (pin "1") (pinfunction "1_1") (pintype "passive"))
    )
    (net (code "14") (name "/P0_5") (class "Default")
      (node (ref "R38") (pin "1") (pinfunction "1_1") (pintype "passive"))
    )
    (net (code "15") (name "/P0_6") (class "Default")
      (node (ref "R30") (pin "1") (pinfunction "1_1") (pintype "passive"))
    )
    (net (code "16") (name "/P0_7") (class "Default")
      (node (ref "R37") (pin "1") (pinfunction "1_1") (pintype "passive"))
    )
    (net (code "17") (name "/P0_8") (class "Default")
      (node (ref "R79") (pin "1") (pinfunction "1_1") (pintype "passive"))
    )
    (net (code "18") (name "/P0_9") (class "Default")
      (node (ref "R80") (pin "1") (pinfunction "1_1") (pintype "passive"))
    )
    (net (code "19") (name "/P0_23") (class "Default")
      (node (ref "U6") (pin "3") (pinfunction "X_3") (pintype "bidirectional"))
    )
    (net (code "20") (name "/P0_24") (class "Default")
      (node (ref "U10") (pin "3") (pinfunction "X_3") (pintype "bidirectional"))
    )
    (net (code "21") (name "/P0_25") (class "Default")
      (node (ref "C28") (pin "1") (pinfunction "1_1") (pintype "passive"))
      (node (ref "R40") (pin "1") (pinfunction "1_1") (pintype "passive"))
      (node (ref "R41") (pin "1") (pinfunction "1_1") (pintype "passive"))
    )
    (net (code "22") (name "/P0_27") (class "Default")
      (node (ref "D11") (pin "2") (pinfunction "K_2") (pintype "passive"))
      (node (ref "R71") (pin "1") (pinfunction "1_1") (pintype "passive"))
    )
    (net (code "23") (name "/P0_28") (class "Default")
      (node (ref "U10") (pin "11") (pinfunction "A_11") (pintype "input"))
      (node (ref "U6") (pin "11") (pinfunction "A_11") (pintype "input"))
    )
    (net (code "24") (name "/P0_29") (class "Default")
      (node (ref "R72") (pin "1") (pinfunction "1_1") (pintype "passive"))
    )
    (net (code "25") (name "/P1_30") (class "Default")
      (node (ref "U10") (pin "10") (pinfunction "B_10") (pintype "input"))
      (node (ref "U6") (pin "10") (pinfunction "B_10") (pintype "input"))
    )
    (net (code "26") (name "/P3_25") (class "Default")
      (node (ref "R84") (pin "1") (pinfunction "1_1") (pintype "passive"))
    )
    (net (code "27") (name "/P3_26") (class "Default")
      (node (ref "U10") (pin "9") (pinfunction "C_9") (pintype "input"))
      (node (ref "U6") (pin "9") (pinfunction "C_9") (pintype "input"))
    )
    (net (code "28") (name "/REL1") (class "Default")
      (node (ref "Q7") (pin "5") (pinfunction "D_5") (pintype "passive"))
      (node (ref "Q7") (pin "6") (pinfunction "D_6") (pintype "passive"))
    )
    (net (code "29") (name "/REL2") (class "Default")
      (node (ref "Q7") (pin "7") (pinfunction "D_7") (pintype "passive"))
      (node (ref "Q7") (pin "8") (pinfunction "D_8") (pintype "passive"))
    )
    (net (code "30") (name "/REL3") (class "Default")
      (node (ref "Q8") (pin "5") (pinfunction "D_5") (pintype "passive"))
      (node (ref "Q8") (pin "6") (pinfunction "D_6") (pintype "passive"))
    )
    (net (code "31") (name "/REL4") (class "Default")
      (node (ref "Q8") (pin "7") (pinfunction "D_7") (pintype "passive"))
      (node (ref "Q8") (pin "8") (pinfunction "D_8") (pintype "passive"))
    )
    (net (code "32") (name "/REL5") (class "Default")
      (node (ref "Q9") (pin "5") (pinfunction "D_5") (pintype "passive"))
      (node (ref "Q9") (pin "6") (pinfunction "D_6") (pintype "passive"))
    )
    (net (code "33") (name "/REL6") (class "Default")
      (node (ref "Q9") (pin "7") (pinfunction "D_7") (pintype "passive"))
      (node (ref "Q9") (pin "8") (pinfunction "D_8") (pintype "passive"))
    )
    (net (code "34") (name "/REL7") (class "Default")
      (node (ref "Q1") (pin "3") (pinfunction "D_3") (pintype "passive"))
    )
    (net (code "35") (name "/SK1") (class "Default")
      (node (ref "R43") (pin "1") (pinfunction "1_1") (pintype "passive"))
    )
    (net (code "36") (name "/SK2") (class "Default")
      (node (ref "R45") (pin "1") (pinfunction "1_1") (pintype "passive"))
    )
    (net (code "37") (name "/SK3") (class "Default")
      (node (ref "R49") (pin "1") (pinfunction "1_1") (pintype "passive"))
    )
    (net (code "38") (name "/SK4") (class "Default")
      (node (ref "R51") (pin "1") (pinfunction "1_1") (pintype "passive"))
    )
    (net (code "39") (name "/U1") (class "Default")
      (node (ref "U10") (pin "13") (pinfunction "X0_13") (pintype "bidirectional"))
    )
    (net (code "40") (name "/U2") (class "Default")
      (node (ref "U10") (pin "14") (pinfunction "X1_14") (pintype "bidirectional"))
    )
    (net (code "41") (name "/Ub1") (class "Default")
      (node (ref "R25") (pin "2") (pinfunction "2_2") (pintype "passive"))
    )
    (net (code "42") (name "/Ub2") (class "Default")
      (node (ref "R29") (pin "2") (pinfunction "2_2") (pintype "passive"))
    )
    (net (code "43") (name "/Ubm1") (class "Default")
      (node (ref "R27") (pin "2") (pinfunction "2_2") (pintype "passive"))
    )
    (net (code "44") (name "/Ubm2") (class "Default")
      (node (ref "R33") (pin "2") (pinfunction "2_2") (pintype "passive"))
    )
    (net (code "45") (name "/Uib1") (class "Default")
      (node (ref "C65") (pin "2") (pinfunction "2_2") (pintype "passive"))
      (node (ref "R122") (pin "2") (pinfunction "2_2") (pintype "passive"))
      (node (ref "R126") (pin "1") (pinfunction "1_1") (pintype "passive"))
    )
    (net (code "46") (name "/Uib2") (class "Default")
      (node (ref "C16") (pin "2") (pinfunction "2_2") (pintype "passive"))
      (node (ref "R62") (pin "2") (pinfunction "2_2") (pintype "passive"))
      (node (ref "R66") (pin "1") (pinfunction "1_1") (pintype "passive"))
    )
    (net (code "47") (name "/Uload") (class "Default")
      (node (ref "R36") (pin "2") (pinfunction "2_2") (pintype "passive"))
    )
    (net (code "48") (name "/Us") (class "Default")
      (node (ref "R41") (pin "2") (pinfunction "2_2") (pintype "passive"))
    )
    (net (code "49") (name "/Uu1") (class "Default")
      (node (ref "C4") (pin "1") (pinfunction "1_1") (pintype "passive"))
      (node (ref "R24") (pin "1") (pinfunction "1_1") (pintype "passive"))
      (node (ref "R25") (pin "1") (pinfunction "1_1") (pintype "passive"))
      (node (ref "U6") (pin "15") (pinfunction "X2_15") (pintype "bidirectional"))
    )
    (net (code "50") (name "/Uu2") (class "Default")
      (node (ref "C5") (pin "1") (pinfunction "1_1") (pintype "passive"))
      (node (ref "R26") (pin "1") (pinfunction "1_1") (pintype "passive"))
      (node (ref "R27") (pin "1") (pinfunction "1_1") (pintype "passive"))
      (node (ref "U6") (pin "14") (pinfunction "X1_14") (pintype "bidirectional"))
    )
    (net (code "51") (name "/Uu3") (class "Default")
      (node (ref "C6") (pin "1") (pinfunction "1_1") (pintype "passive"))
      (node (ref "R28") (pin "1") (pinfunction "1_1") (pintype "passive"))
      (node (ref "R29") (pin "1") (pinfunction "1_1") (pintype "passive"))
      (node (ref "U6") (pin "13") (pinfunction "X0_13") (pintype "bidirectional"))
    )
    (net (code "52") (name "/Uu4") (class "Default")
      (node (ref "C7") (pin "1") (pinfunction "1_1") (pintype "passive"))
      (node (ref "R32") (pin "1") (pinfunction "1_1") (pintype "passive"))
      (node (ref "R33") (pin "1") (pinfunction "1_1") (pintype "passive"))
      (node (ref "U6") (pin "1") (pinfunction "X4_1") (pintype "bidirectional"))
    )
    (net (code "53") (name "/Uu5") (class "Default")
      (node (ref "C9") (pin "1") (pinfunction "1_1") (pintype "passive"))
      (node (ref "D6") (pin "2") (pinfunction "K_2") (pintype "passive"))
      (node (ref "R47") (pin "2") (pinfunction "2_2") (pintype "passive"))
      (node (ref "R48") (pin "2") (pinfunction "2_2") (pintype "passive"))
      (node (ref "U6") (pin "2") (pinfunction "X6_2") (pintype "bidirectional"))
    )
    (net (code "54") (name "/Uu6") (class "Default")
      (node (ref "C10") (pin "1") (pinfunction "1_1") (pintype "passive"))
      (node (ref "D7") (pin "2") (pinfunction "K_2") (pintype "passive"))
      (node (ref "R54") (pin "2") (pinfunction "2_2") (pintype "passive"))
      (node (ref "R55") (pin "2") (pinfunction "2_2") (pintype "passive"))
      (node (ref "U6") (pin "4") (pinfunction "X7_4") (pintype "bidirectional"))
    )
    (net (code "55") (name "/Uu7") (class "Default")
      (node (ref "C13") (pin "1") (pinfunction "1_1") (pintype "passive"))
      (node (ref "D8") (pin "2") (pinfunction "K_2") (pintype "passive"))
      (node (ref "R58") (pin "2") (pinfunction "2_2") (pintype "passive"))
      (node (ref "R59") (pin "2") (pinfunction "2_2") (pintype "passive"))
      (node (ref "U6") (pin "5") (pinfunction "X5_5") (pintype "bidirectional"))
    )
    (net (code "56") (name "/Uu8") (class "Default")
      (node (ref "C24") (pin "1") (pinfunction "1_1") (pintype "passive"))
      (node (ref "D9") (pin "2") (pinfunction "K_2") (pintype "passive"))
      (node (ref "R68") (pin "2") (pinfunction "2_2") (pintype "passive"))
      (node (ref "R70") (pin "2") (pinfunction "2_2") (pintype "passive"))
      (node (ref "U6") (pin "12") (pinfunction "X3_12") (pintype "bidirectional"))
    )
    (net (code "57") (name "/Uu9") (class "Default")
      (node (ref "C8") (pin "1") (pinfunction "1_1") (pintype "passive"))
      (node (ref "R35") (pin "1") (pinfunction "1_1") (pintype "passive"))
      (node (ref "R36") (pin "1") (pinfunction "1_1") (pintype "passive"))
      (node (ref "U10") (pin "1") (pinfunction "X4_1") (pintype "bidirectional"))
    )
    (net (code "58") (name "/Uu10") (class "Default")
      (node (ref "C40") (pin "1") (pinfunction "1_1") (pintype "passive"))
      (node (ref "D13") (pin "2") (pinfunction "K_2") (pintype "passive"))
      (node (ref "R111") (pin "2") (pinfunction "2_2") (pintype "passive"))
      (node (ref "R51") (pin "2") (pinfunction "2_2") (pintype "passive"))
      (node (ref "U10") (pin "2") (pinfunction "X6_2") (pintype "bidirectional"))
    )
    (net (code "59") (name "/Uu11") (class "Default")
      (node (ref "C38") (pin "1") (pinfunction "1_1") (pintype "passive"))
      (node (ref "D4") (pin "2") (pinfunction "K_2") (pintype "passive"))
      (node (ref "R118") (pin "2") (pinfunction "2_2") (pintype "passive"))
      (node (ref "R49") (pin "2") (pinfunction "2_2") (pintype "passive"))
      (node (ref "U10") (pin "4") (pinfunction "X7_4") (pintype "bidirectional"))
    )
    (net (code "60") (name "/Uu12") (class "Default")
      (node (ref "C39") (pin "1") (pinfunction "1_1") (pintype "passive"))
      (node (ref "D12") (pin "2") (pinfunction "K_2") (pintype "passive"))
      (node (ref "R129") (pin "2") (pinfunction "2_2") (pintype "passive"))
      (node (ref "R45") (pin "2") (pinfunction "2_2") (pintype "passive"))
      (node (ref "U10") (pin "5") (pinfunction "X5_5") (pintype "bidirectional"))
    )
    (net (code "61") (name "/Uu13") (class "Default")
      (node (ref "C37") (pin "1") (pinfunction "1_1") (pintype "passive"))
      (node (ref "D3") (pin "2") (pinfunction "K_2") (pintype "passive"))
      (node (ref "R128") (pin "2") (pinfunction "2_2") (pintype "passive"))
      (node (ref "R43") (pin "2") (pinfunction "2_2") (pintype "passive"))
      (node (ref "U10") (pin "12") (pinfunction "X3_12") (pintype "bidirectional"))
    )
    (net (code "62") (name "/Uu14") (class "Default")
      (node (ref "C26") (pin "1") (pinfunction "1_1") (pintype "passive"))
      (node (ref "D10") (pin "2") (pinfunction "K_2") (pintype "passive"))
      (node (ref "R75") (pin "2") (pinfunction "2_2") (pintype "passive"))
      (node (ref "R76") (pin "2") (pinfunction "2_2") (pintype "passive"))
      (node (ref "U10") (pin "15") (pinfunction "X2_15") (pintype "bidirectional"))
    )
    (net (code "63") (name "/Vs") (class "Default")
      (node (ref "R71") (pin "2") (pinfunction "2_2") (pintype "passive"))
    )
    (net (code "64") (name "GND") (class "Default")
      (node (ref "C10") (pin "2") (pinfunction "2_2") (pintype "passive"))
      (node (ref "C12") (pin "1") (pinfunction "1_1") (pintype "passive"))
      (node (ref "C13") (pin "2") (pinfunction "2_2") (pintype "passive"))
      (node (ref "C14") (pin "1") (pinfunction "1_1") (pintype "passive"))
      (node (ref "C15") (pin "1") (pinfunction "1_1") (pintype "passive"))
      (node (ref "C16") (pin "1") (pinfunction "1_1") (pintype "passive"))
      (node (ref "C17") (pin "1") (pinfunction "1_1") (pintype "passive"))
      (node (ref "C18") (pin "1") (pinfunction "1_1") (pintype "passive"))
      (node (ref "C19") (pin "1") (pinfunction "1_1") (pintype "passive"))
      (node (ref "C20") (pin "1") (pinfunction "1_1") (pintype "passive"))
      (node (ref "C23") (pin "2") (pinfunction "2_2") (pintype "passive"))
      (node (ref "C24") (pin "2") (pinfunction "2_2") (pintype "passive"))
      (node (ref "C25") (pin "1") (pinfunction "1_1") (pintype "passive"))
      (node (ref "C26") (pin "2") (pinfunction "2_2") (pintype "passive"))
      (node (ref "C28") (pin "2") (pinfunction "2_2") (pintype "passive"))
      (node (ref "C37") (pin "2") (pinfunction "2_2") (pintype "passive"))
      (node (ref "C38") (pin "2") (pinfunction "2_2") (pintype "passive"))
      (node (ref "C39") (pin "2") (pinfunction "2_2") (pintype "passive"))
      (node (ref "C4") (pin "2") (pinfunction "2_2") (pintype "passive"))
      (node (ref "C40") (pin "2") (pinfunction "2_2") (pintype "passive"))
      (node (ref "C5") (pin "2") (pinfunction "2_2") (pintype "passive"))
      (node (ref "C6") (pin "2") (pinfunction "2_2") (pintype "passive"))
      (node (ref "C62") (pin "1") (pinfunction "1_1") (pintype "passive"))
      (node (ref "C63") (pin "1") (pinfunction "1_1") (pintype "passive"))
      (node (ref "C64") (pin "1") (pinfunction "1_1") (pintype "passive"))
      (node (ref "C65") (pin "1") (pinfunction "1_1") (pintype "passive"))
      (node (ref "C66") (pin "2") (pinfunction "2_2") (pintype "passive"))
      (node (ref "C7") (pin "2") (pinfunction "2_2") (pintype "passive"))
      (node (ref "C8") (pin "2") (pinfunction "2_2") (pintype "passive"))
      (node (ref "C9") (pin "2") (pinfunction "2_2") (pintype "passive"))
      (node (ref "D10") (pin "1") (pinfunction "A_1") (pintype "passive"))
      (node (ref "D11") (pin "1") (pinfunction "A_1") (pintype "passive"))
      (node (ref "D12") (pin "1") (pinfunction "A_1") (pintype "passive"))
      (node (ref "D13") (pin "1") (pinfunction "A_1") (pintype "passive"))
      (node (ref "D3") (pin "1") (pinfunction "A_1") (pintype "passive"))
      (node (ref "D4") (pin "1") (pinfunction "A_1") (pintype "passive"))
      (node (ref "D6") (pin "1") (pinfunction "A_1") (pintype "passive"))
      (node (ref "D7") (pin "1") (pinfunction "A_1") (pintype "passive"))
      (node (ref "D8") (pin "1") (pinfunction "A_1") (pintype "passive"))
      (node (ref "D9") (pin "1") (pinfunction "A_1") (pintype "passive"))
      (node (ref "Q1") (pin "2") (pinfunction "S_2") (pintype "passive"))
      (node (ref "Q6") (pin "2") (pinfunction "E_2") (pintype "passive"))
      (node (ref "Q7") (pin "1") (pinfunction "S_1") (pintype "passive"))
      (node (ref "Q7") (pin "3") (pinfunction "S_3") (pintype "passive"))
      (node (ref "Q8") (pin "1") (pinfunction "S_1") (pintype "passive"))
      (node (ref "Q8") (pin "3") (pinfunction "S_3") (pintype "passive"))
      (node (ref "Q9") (pin "1") (pinfunction "S_1") (pintype "passive"))
      (node (ref "Q9") (pin "3") (pinfunction "S_3") (pintype "passive"))
      (node (ref "R1") (pin "1") (pinfunction "1_1") (pintype "passive"))
      (node (ref "R127") (pin "1") (pinfunction "1_1") (pintype "passive"))
      (node (ref "R24") (pin "2") (pinfunction "2_2") (pintype "passive"))
      (node (ref "R26") (pin "2") (pinfunction "2_2") (pintype "passive"))
      (node (ref "R28") (pin "2") (pinfunction "2_2") (pintype "passive"))
      (node (ref "R32") (pin "2") (pinfunction "2_2") (pintype "passive"))
      (node (ref "R34") (pin "1") (pinfunction "1_1") (pintype "passive"))
      (node (ref "R35") (pin "2") (pinfunction "2_2") (pintype "passive"))
      (node (ref "R39") (pin "1") (pinfunction "1_1") (pintype "passive"))
      (node (ref "R40") (pin "2") (pinfunction "2_2") (pintype "passive"))
      (node (ref "R48") (pin "1") (pinfunction "1_1") (pintype "passive"))
      (node (ref "R55") (pin "1") (pinfunction "1_1") (pintype "passive"))
      (node (ref "R59") (pin "1") (pinfunction "1_1") (pintype "passive"))
      (node (ref "R69") (pin "1") (pinfunction "1_1") (pintype "passive"))
      (node (ref "R70") (pin "1") (pinfunction "1_1") (pintype "passive"))
      (node (ref "R74") (pin "1") (pinfunction "1_1") (pintype "passive"))
      (node (ref "R76") (pin "1") (pinfunction "1_1") (pintype "passive"))
      (node (ref "R77") (pin "1") (pinfunction "1_1") (pintype "passive"))
      (node (ref "R78") (pin "1") (pinfunction "1_1") (pintype "passive"))
      (node (ref "R81") (pin "1") (pinfunction "1_1") (pintype "passive"))
      (node (ref "R82") (pin "1") (pinfunction "1_1") (pintype "passive"))
      (node (ref "U10") (pin "6") (pinfunction "INH_6") (pintype "input"))
      (node (ref "U10") (pin "7") (pinfunction "VEE_7") (pintype "power_in"))
      (node (ref "U10") (pin "8") (pinfunction "VSS_8") (pintype "power_in"))
      (node (ref "U6") (pin "6") (pinfunction "INH_6") (pintype "input"))
      (node (ref "U6") (pin "7") (pinfunction "VEE_7") (pintype "power_in"))
      (node (ref "U6") (pin "8") (pinfunction "VSS_8") (pintype "power_in"))
    )
    (net (code "65") (name "Net-(C12-Pad2)") (class "Default")
      (node (ref "C12") (pin "2") (pinfunction "2_2") (pintype "passive"))
      (node (ref "K1") (pin "3") (pinfunction "3_3") (pintype "passive"))
      (node (ref "R60") (pin "1") (pinfunction "1_1") (pintype "passive"))
      (node (ref "R61") (pin "1") (pinfunction "1_1") (pintype "passive"))
    )
    (net (code "66") (name "Net-(C14-Pad2)") (class "Default")
      (node (ref "C14") (pin "2") (pinfunction "2_2") (pintype "passive"))
      (node (ref "K1") (pin "1") (pinfunction "1_1") (pintype "passive"))
      (node (ref "R64") (pin "1") (pinfunction "1_1") (pintype "passive"))
      (node (ref "R65") (pin "1") (pinfunction "1_1") (pintype "passive"))
    )
    (net (code "67") (name "Net-(C62-Pad2)") (class "Default")
      (node (ref "C62") (pin "2") (pinfunction "2_2") (pintype "passive"))
      (node (ref "K2") (pin "3") (pinfunction "3_3") (pintype "passive"))
      (node (ref "R121") (pin "1") (pinfunction "1_1") (pintype "passive"))
      (node (ref "R13") (pin "1") (pinfunction "1_1") (pintype "passive"))
    )
    (net (code "68") (name "Net-(C63-Pad2)") (class "Default")
      (node (ref "C63") (pin "2") (pinfunction "2_2") (pintype "passive"))
      (node (ref "K2") (pin "1") (pinfunction "1_1") (pintype "passive"))
      (node (ref "R124") (pin "1") (pinfunction "1_1") (pintype "passive"))
      (node (ref "R125") (pin "1") (pinfunction "1_1") (pintype "passive"))
    )
    (net (code "69") (name "Net-(D5-A)") (class "Default")
      (node (ref "D5") (pin "1") (pinfunction "A_1") (pintype "passive"))
      (node (ref "K1") (pin "5") (pinfunction "5_5") (pintype "passive"))
      (node (ref "K2") (pin "5") (pinfunction "5_5") (pintype "passive"))
      (node (ref "Q6") (pin "3") (pinfunction "C_3") (pintype "passive"))
    )
    (net (code "70") (name "Net-(Q1-G)") (class "Default")
      (node (ref "Q1") (pin "1") (pinfunction "G_1") (pintype "passive"))
      (node (ref "R1") (pin "2") (pinfunction "2_2") (pintype "passive"))
      (node (ref "R84") (pin "2") (pinfunction "2_2") (pintype "passive"))
    )
    (net (code "71") (name "Net-(Q6-B)") (class "Default")
      (node (ref "Q6") (pin "1") (pinfunction "B_1") (pintype "passive"))
      (node (ref "R72") (pin "2") (pinfunction "2_2") (pintype "passive"))
      (node (ref "R74") (pin "2") (pinfunction "2_2") (pintype "passive"))
    )
    (net (code "72") (name "Net-(Q7A-G)") (class "Default")
      (node (ref "Q7") (pin "2") (pinfunction "G_2") (pintype "passive"))
      (node (ref "R31") (pin "2") (pinfunction "2_2") (pintype "passive"))
      (node (ref "R34") (pin "2") (pinfunction "2_2") (pintype "passive"))
    )
    (net (code "73") (name "Net-(Q7B-G)") (class "Default")
      (node (ref "Q7") (pin "4") (pinfunction "G_4") (pintype "passive"))
      (node (ref "R38") (pin "2") (pinfunction "2_2") (pintype "passive"))
      (node (ref "R39") (pin "2") (pinfunction "2_2") (pintype "passive"))
    )
    (net (code "74") (name "Net-(Q8A-G)") (class "Default")
      (node (ref "Q8") (pin "2") (pinfunction "G_2") (pintype "passive"))
      (node (ref "R30") (pin "2") (pinfunction "2_2") (pintype "passive"))
      (node (ref "R77") (pin "2") (pinfunction "2_2") (pintype "passive"))
    )
    (net (code "75") (name "Net-(Q8B-G)") (class "Default")
      (node (ref "Q8") (pin "4") (pinfunction "G_4") (pintype "passive"))
      (node (ref "R37") (pin "2") (pinfunction "2_2") (pintype "passive"))
      (node (ref "R78") (pin "2") (pinfunction "2_2") (pintype "passive"))
    )
    (net (code "76") (name "Net-(Q9A-G)") (class "Default")
      (node (ref "Q9") (pin "2") (pinfunction "G_2") (pintype "passive"))
      (node (ref "R79") (pin "2") (pinfunction "2_2") (pintype "passive"))
      (node (ref "R81") (pin "2") (pinfunction "2_2") (pintype "passive"))
    )
    (net (code "77") (name "Net-(Q9B-G)") (class "Default")
      (node (ref "Q9") (pin "4") (pinfunction "G_4") (pintype "passive"))
      (node (ref "R80") (pin "2") (pinfunction "2_2") (pintype "passive"))
      (node (ref "R82") (pin "2") (pinfunction "2_2") (pintype "passive"))
    )
    (net (code "78") (name "Net-(U2-IN+)") (class "Default")
      (node (ref "C66") (pin "1") (pinfunction "1_1") (pintype "passive"))
      (node (ref "R125") (pin "2") (pinfunction "2_2") (pintype "passive"))
      (node (ref "R127") (pin "2") (pinfunction "2_2") (pintype "passive"))
      (node (ref "U2") (pin "3") (pinfunction "IN+_3") (pintype "input"))
    )
    (net (code "79") (name "Net-(U2-IN-)") (class "Default")
      (node (ref "C61") (pin "2") (pinfunction "2_2") (pintype "passive"))
      (node (ref "R12") (pin "1") (pinfunction "1_1") (pintype "passive"))
      (node (ref "R121") (pin "2") (pinfunction "2_2") (pintype "passive"))
      (node (ref "U2") (pin "2") (pinfunction "IN-_2") (pintype "input"))
    )
    (net (code "80") (name "Net-(U2-OUT)") (class "Default")
      (node (ref "C61") (pin "1") (pinfunction "1_1") (pintype "passive"))
      (node (ref "C64") (pin "2") (pinfunction "2_2") (pintype "passive"))
      (node (ref "R12") (pin "2") (pinfunction "2_2") (pintype "passive"))
      (node (ref "R122") (pin "1") (pinfunction "1_1") (pintype "passive"))
      (node (ref "U2") (pin "6") (pinfunction "OUT_6") (pintype "output"))
    )
    (net (code "81") (name "Net-(U9-IN+)") (class "Default")
      (node (ref "C23") (pin "1") (pinfunction "1_1") (pintype "passive"))
      (node (ref "R65") (pin "2") (pinfunction "2_2") (pintype "passive"))
      (node (ref "R69") (pin "2") (pinfunction "2_2") (pintype "passive"))
      (node (ref "U9") (pin "3") (pinfunction "IN+_3") (pintype "input"))
    )
    (net (code "82") (name "Net-(U9-IN-)") (class "Default")
      (node (ref "C11") (pin "2") (pinfunction "2_2") (pintype "passive"))
      (node (ref "R57") (pin "1") (pinfunction "1_1") (pintype "passive"))
      (node (ref "R61") (pin "2") (pinfunction "2_2") (pintype "passive"))
      (node (ref "U9") (pin "2") (pinfunction "IN-_2") (pintype "input"))
    )
    (net (code "83") (name "Net-(U9-OUT)") (class "Default")
      (node (ref "C11") (pin "1") (pinfunction "1_1") (pintype "passive"))
      (node (ref "C15") (pin "2") (pinfunction "2_2") (pintype "passive"))
      (node (ref "R57") (pin "2") (pinfunction "2_2") (pintype "passive"))
      (node (ref "R62") (pin "1") (pinfunction "1_1") (pintype "passive"))
      (node (ref "U9") (pin "6") (pinfunction "OUT_6") (pintype "output"))
    )
    (net (code "84") (name "Vref") (class "Default")
      (node (ref "C20") (pin "2") (pinfunction "2_2") (pintype "passive"))
      (node (ref "C25") (pin "2") (pinfunction "2_2") (pintype "passive"))
      (node (ref "R126") (pin "2") (pinfunction "2_2") (pintype "passive"))
      (node (ref "R66") (pin "2") (pinfunction "2_2") (pintype "passive"))
    )
    (net (code "85") (name "unconnected-(K1-Pad2)") (class "Default")
      (node (ref "K1") (pin "2") (pinfunction "2_2") (pintype "passive"))
    )
    (net (code "86") (name "unconnected-(K2-Pad2)") (class "Default")
      (node (ref "K2") (pin "2") (pinfunction "2_2") (pintype "passive"))
    )
    (net (code "87") (name "unconnected-(U2-NC-Pad5)") (class "Default")
      (node (ref "U2") (pin "5") (pinfunction "NC_5") (pintype "passive"))
    )
    (net (code "88") (name "unconnected-(U2-VOSTRIM-Pad1)") (class "Default")
      (node (ref "U2") (pin "1") (pinfunction "VOSTRIM_1") (pintype "passive"))
    )
    (net (code "89") (name "unconnected-(U2-VOSTRIM-Pad8)") (class "Default")
      (node (ref "U2") (pin "8") (pinfunction "VOSTRIM_8") (pintype "passive"))
    )
    (net (code "90") (name "unconnected-(U9-NC-Pad5)") (class "Default")
      (node (ref "U9") (pin "5") (pinfunction "NC_5") (pintype "passive"))
    )
    (net (code "91") (name "unconnected-(U9-VOSTRIM-Pad1)") (class "Default")
      (node (ref "U9") (pin "1") (pinfunction "VOSTRIM_1") (pintype "passive"))
    )
    (net (code "92") (name "unconnected-(U9-VOSTRIM-Pad8)") (class "Default")
      (node (ref "U9") (pin "8") (pinfunction "VOSTRIM_8") (pintype "passive"))
    )
  )
)
